# Schematic.net
KiCad netlist of a schematic drawn in Altium Designer
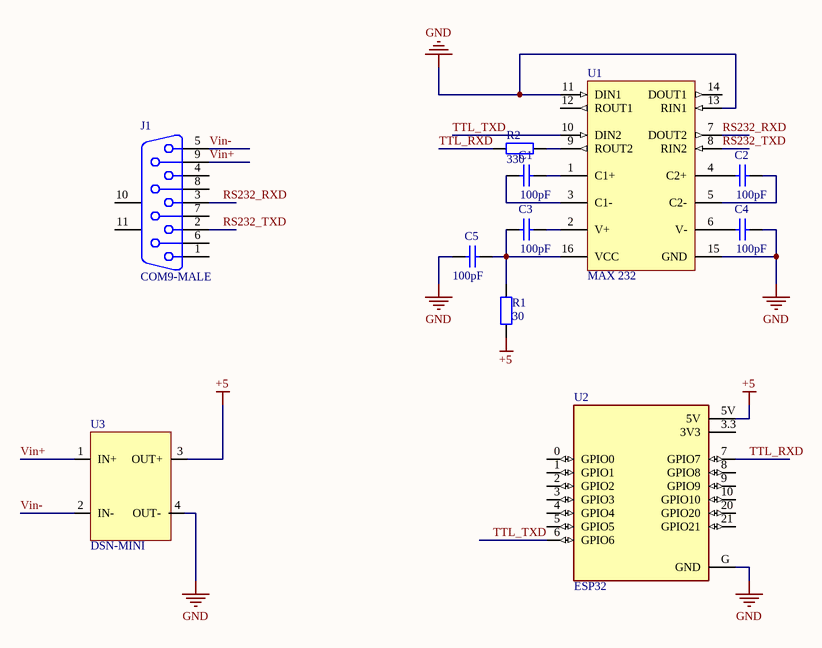
[diagram p0: Schematic.SchDoc]

(export (version "E")
  (design (tool "Eeschema 10.0.6"))
  (components
    (comp (ref "C1")
      (value "100pF")
      (footprint "C1206")
      (description "Capacitor (Semiconductor SIM Model)")
      (fields (field (name "Comment") "Cap Semi") (field (name "PUBLISHER") "Altium Limited"))
      (libsource (lib "Miscellaneous Devices") (part "Cap Semi"))
    )
    (comp (ref "C2")
      (value "100pF")
      (footprint "C1206")
      (description "Capacitor (Semiconductor SIM Model)")
      (fields (field (name "Comment") "Cap Semi") (field (name "PUBLISHER") "Altium Limited"))
      (libsource (lib "Miscellaneous Devices") (part "Cap Semi"))
    )
    (comp (ref "C3")
      (value "100pF")
      (footprint "C1206")
      (description "Capacitor (Semiconductor SIM Model)")
      (fields (field (name "Comment") "Cap Semi") (field (name "PUBLISHER") "Altium Limited"))
      (libsource (lib "Miscellaneous Devices") (part "Cap Semi"))
    )
    (comp (ref "C4")
      (value "100pF")
      (footprint "C1206")
      (description "Capacitor (Semiconductor SIM Model)")
      (fields (field (name "Comment") "Cap Semi") (field (name "PUBLISHER") "Altium Limited"))
      (libsource (lib "Miscellaneous Devices") (part "Cap Semi"))
    )
    (comp (ref "C5")
      (value "100pF")
      (footprint "C1206")
      (description "Capacitor (Semiconductor SIM Model)")
      (fields (field (name "Comment") "Cap Semi") (field (name "PUBLISHER") "Altium Limited"))
      (libsource (lib "Miscellaneous Devices") (part "Cap Semi"))
    )
    (comp (ref "J1")
      (value "COM9-MALE")
      (footprint "DSUB1.385-2H9")
      (description "Receptacle Assembly, 9 Position, Right Angle")
      (fields (field (name "PUBLISHER") "Altium Limited"))
      (libsource (lib "Miscellaneous Connectors") (part "D Connector 9"))
    )
    (comp (ref "R1")
      (value "30")
      (footprint "RESC-1206 (3216)")
      (description "RES SMD 0.0 OHM JUMPER 1/4W 1206")
      (fields (field (name "MPN") "RC1206JR-070RL"))
      (libsource (lib "") (part "RC1206JR-070RL_1"))
    )
    (comp (ref "R2")
      (value "330")
      (footprint "RESC-1206 (3216)")
      (description "RES SMD 0.0 OHM JUMPER 1/4W 1206")
      (fields (field (name "MPN") "RC1206JR-070RL"))
      (libsource (lib "BYTECH_HW_LIB_2019") (part "RC1206JR-070RL"))
    )
    (comp (ref "U1")
      (value "MAX 232")
      (footprint "SOIC-16")
      (description "IC DRVR/RCVR MULTCH RS232 16SOIC")
      (fields (field (name "MPN") "MAX3232CDRE4, MAX3232CDR"))
      (libsource (lib "BYTECH_HW_LIB_2019") (part "MAX3232CDRE4, MAX3232CDR"))
    )
    (comp (ref "U2")
      (value "ESP32")
      (footprint "MODULE_ESP32-C3_SUPERMINI")
      (description "Super tiny ESP32-C3 board")
      (fields (field (name "MF") "Espressif Systems") (field (name "MP") "ESP32-C3 SuperMini"))
      (libsource (lib "PCB_GTIL_WIFI_MODULE") (part "ESP32-C3_SUPERMINI"))
    )
    (comp (ref "U3")
      (value "DSN-MINI")
      (footprint "PCBComponent_1")
      (libsource (lib "DSN-MINI-360") (part "DSN-MINI"))
    )
  )
  (nets
    (net (code "1") (name "+5") (class "Default")
      (node (ref "R1") (pin "1") (pinfunction "1_1") (pintype "passive"))
      (node (ref "U2") (pin "5V") (pinfunction "5V_5V") (pintype "power_in"))
      (node (ref "U3") (pin "3") (pinfunction "OUT+_3") (pintype "power_in"))
    )
    (net (code "2") (name "/RS232_RXD") (class "Default")
      (node (ref "J1") (pin "3") (pinfunction "3_3") (pintype "passive"))
      (node (ref "U1") (pin "7") (pinfunction "DOUT2_7") (pintype "output"))
    )
    (net (code "3") (name "/RS232_TXD") (class "Default")
      (node (ref "J1") (pin "2") (pinfunction "2_2") (pintype "passive"))
      (node (ref "U1") (pin "8") (pinfunction "RIN2_8") (pintype "input"))
    )
    (net (code "4") (name "/TTL_RXD") (class "Default")
      (node (ref "R2") (pin "2") (pinfunction "2_2") (pintype "passive"))
      (node (ref "U2") (pin "7") (pinfunction "GPIO7_7") (pintype "bidirectional"))
    )
    (net (code "5") (name "/TTL_TXD") (class "Default")
      (node (ref "U1") (pin "10") (pinfunction "DIN2_10") (pintype "input"))
      (node (ref "U2") (pin "6") (pinfunction "GPIO6_6") (pintype "bidirectional"))
    )
    (net (code "6") (name "/Vin+") (class "Default")
      (node (ref "J1") (pin "9") (pinfunction "9_9") (pintype "passive"))
      (node (ref "U3") (pin "1") (pinfunction "IN+_1") (pintype "power_in"))
    )
    (net (code "7") (name "/Vin-") (class "Default")
      (node (ref "J1") (pin "5") (pinfunction "5_5") (pintype "passive"))
      (node (ref "U3") (pin "2") (pinfunction "IN-_2") (pintype "passive"))
    )
    (net (code "8") (name "GND") (class "Default")
      (node (ref "C4") (pin "2") (pinfunction "2_2") (pintype "passive"))
      (node (ref "C5") (pin "1") (pinfunction "1_1") (pintype "passive"))
      (node (ref "U1") (pin "11") (pinfunction "DIN1_11") (pintype "input"))
      (node (ref "U1") (pin "13") (pinfunction "RIN1_13") (pintype "input"))
      (node (ref "U1") (pin "15") (pinfunction "GND_15") (pintype "power_in"))
      (node (ref "U2") (pin "G") (pinfunction "GND_G") (pintype "power_in"))
      (node (ref "U3") (pin "4") (pinfunction "OUT-_4") (pintype "passive"))
    )
    (net (code "9") (name "Net-(U1-C1+)") (class "Default")
      (node (ref "C1") (pin "2") (pinfunction "2_2") (pintype "passive"))
      (node (ref "U1") (pin "1") (pinfunction "C1+_1") (pintype "passive"))
    )
    (net (code "10") (name "Net-(U1-C1-)") (class "Default")
      (node (ref "C1") (pin "1") (pinfunction "1_1") (pintype "passive"))
      (node (ref "U1") (pin "3") (pinfunction "C1-_3") (pintype "passive"))
    )
    (net (code "11") (name "Net-(U1-C2+)") (class "Default")
      (node (ref "C2") (pin "1") (pinfunction "1_1") (pintype "passive"))
      (node (ref "U1") (pin "4") (pinfunction "C2+_4") (pintype "passive"))
    )
    (net (code "12") (name "Net-(U1-C2-)") (class "Default")
      (node (ref "C2") (pin "2") (pinfunction "2_2") (pintype "passive"))
      (node (ref "U1") (pin "5") (pinfunction "C2-_5") (pintype "passive"))
    )
    (net (code "13") (name "Net-(U1-ROUT2)") (class "Default")
      (node (ref "R2") (pin "1") (pinfunction "1_1") (pintype "passive"))
      (node (ref "U1") (pin "9") (pinfunction "ROUT2_9") (pintype "output"))
    )
    (net (code "14") (name "Net-(U1-V+)") (class "Default")
      (node (ref "C3") (pin "2") (pinfunction "2_2") (pintype "passive"))
      (node (ref "U1") (pin "2") (pinfunction "V+_2") (pintype "power_in"))
    )
    (net (code "15") (name "Net-(U1-V-)") (class "Default")
      (node (ref "C4") (pin "1") (pinfunction "1_1") (pintype "passive"))
      (node (ref "U1") (pin "6") (pinfunction "V-_6") (pintype "power_in"))
    )
    (net (code "16") (name "Net-(U1-VCC)") (class "Default")
      (node (ref "C3") (pin "1") (pinfunction "1_1") (pintype "passive"))
      (node (ref "C5") (pin "2") (pinfunction "2_2") (pintype "passive"))
      (node (ref "R1") (pin "2") (pinfunction "2_2") (pintype "passive"))
      (node (ref "U1") (pin "16") (pinfunction "VCC_16") (pintype "power_in"))
    )
    (net (code "17") (name "unconnected-(J1-MH1-Pad10)") (class "Default")
      (node (ref "J1") (pin "10") (pinfunction "MH1_10") (pintype "passive"))
    )
    (net (code "18") (name "unconnected-(J1-MH2-Pad11)") (class "Default")
      (node (ref "J1") (pin "11") (pinfunction "MH2_11") (pintype "passive"))
    )
    (net (code "19") (name "unconnected-(J1-Pad1)") (class "Default")
      (node (ref "J1") (pin "1") (pinfunction "1_1") (pintype "passive"))
    )
    (net (code "20") (name "unconnected-(J1-Pad4)") (class "Default")
      (node (ref "J1") (pin "4") (pinfunction "4_4") (pintype "passive"))
    )
    (net (code "21") (name "unconnected-(J1-Pad6)") (class "Default")
      (node (ref "J1") (pin "6") (pinfunction "6_6") (pintype "passive"))
    )
    (net (code "22") (name "unconnected-(J1-Pad7)") (class "Default")
      (node (ref "J1") (pin "7") (pinfunction "7_7") (pintype "passive"))
    )
    (net (code "23") (name "unconnected-(J1-Pad8)") (class "Default")
      (node (ref "J1") (pin "8") (pinfunction "8_8") (pintype "passive"))
    )
    (net (code "24") (name "unconnected-(U1-DOUT1-Pad14)") (class "Default")
      (node (ref "U1") (pin "14") (pinfunction "DOUT1_14") (pintype "output"))
    )
    (net (code "25") (name "unconnected-(U1-ROUT1-Pad12)") (class "Default")
      (node (ref "U1") (pin "12") (pinfunction "ROUT1_12") (pintype "output"))
    )
    (net (code "26") (name "unconnected-(U2-3V3-Pad3.3)") (class "Default")
      (node (ref "U2") (pin "3.3") (pinfunction "3V3_3.3") (pintype "power_in"))
    )
    (net (code "27") (name "unconnected-(U2-GPIO0-Pad0)") (class "Default")
      (node (ref "U2") (pin "0") (pinfunction "GPIO0_0") (pintype "bidirectional"))
    )
    (net (code "28") (name "unconnected-(U2-GPIO1-Pad1)") (class "Default")
      (node (ref "U2") (pin "1") (pinfunction "GPIO1_1") (pintype "bidirectional"))
    )
    (net (code "29") (name "unconnected-(U2-GPIO2-Pad2)") (class "Default")
      (node (ref "U2") (pin "2") (pinfunction "GPIO2_2") (pintype "bidirectional"))
    )
    (net (code "30") (name "unconnected-(U2-GPIO3-Pad3)") (class "Default")
      (node (ref "U2") (pin "3") (pinfunction "GPIO3_3") (pintype "bidirectional"))
    )
    (net (code "31") (name "unconnected-(U2-GPIO4-Pad4)") (class "Default")
      (node (ref "U2") (pin "4") (pinfunction "GPIO4_4") (pintype "bidirectional"))
    )
    (net (code "32") (name "unconnected-(U2-GPIO5-Pad5)") (class "Default")
      (node (ref "U2") (pin "5") (pinfunction "GPIO5_5") (pintype "bidirectional"))
    )
    (net (code "33") (name "unconnected-(U2-GPIO8-Pad8)") (class "Default")
      (node (ref "U2") (pin "8") (pinfunction "GPIO8_8") (pintype "bidirectional"))
    )
    (net (code "34") (name "unconnected-(U2-GPIO9-Pad9)") (class "Default")
      (node (ref "U2") (pin "9") (pinfunction "GPIO9_9") (pintype "bidirectional"))
    )
    (net (code "35") (name "unconnected-(U2-GPIO10-Pad10)") (class "Default")
      (node (ref "U2") (pin "10") (pinfunction "GPIO10_10") (pintype "bidirectional"))
    )
    (net (code "36") (name "unconnected-(U2-GPIO20-Pad20)") (class "Default")
      (node (ref "U2") (pin "20") (pinfunction "GPIO20_20") (pintype "bidirectional"))
    )
    (net (code "37") (name "unconnected-(U2-GPIO21-Pad21)") (class "Default")
      (node (ref "U2") (pin "21") (pinfunction "GPIO21_21") (pintype "bidirectional"))
    )
  )
)
